# Connectors.net
KiCad netlist of a schematic drawn in Altium Designer
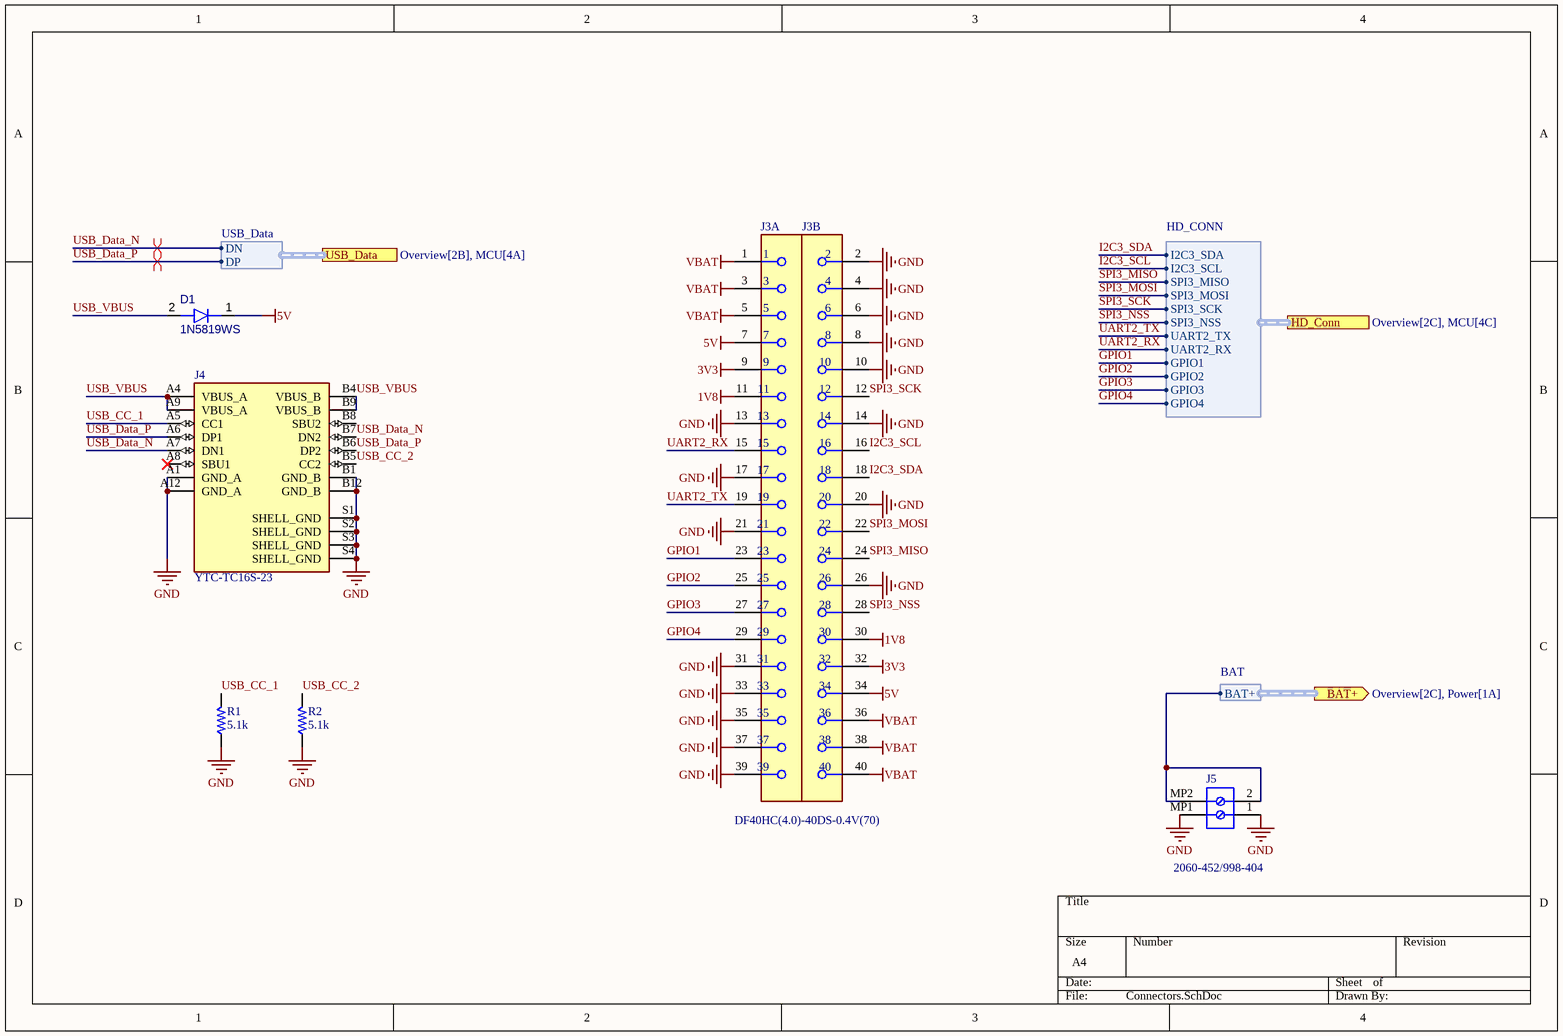
[diagram p0: Connectors.SchDoc]

(export (version "E")
  (design (tool "Eeschema 10.0.6"))
  (components
    (comp (ref "D1")
      (value "1N5819WS")
      (footprint "FP-477-02-IPC_C")
      (description "40V 600mV@1A 1A SOD-323  Schottky Barrier Diodes (SBD) ROHS")
      (fields (field (name "JLCPCB PART NUMBER") "C191023"))
      (libsource (lib "StrathSEDS") (part "DIODE-2"))
    )
    (comp (ref "J3")
      (value "DF40HC(4.0)-40DS-0.4V(70)")
      (footprint "FP-DF40HC_4_0_-40DS-0_4V-MFG")
      (fields (field (name "JLCPCB PART NUMBER") "C3654058"))
      (libsource (lib "StrathSEDS") (part "7acf1c4a8db21028d11741a46a6ec78"))
    )
    (comp (ref "J4")
      (value "YTC-TC16S-23")
      (footprint "VALCON_CSP-USC16-TR")
      (description "YTC-TC16S-23 USB Type C Surface Mount PCB Socket 3A")
      (fields (field (name "MP") "CSP-USC16-TR") (field (name "LCSC PART #") "C2927300"))
      (libsource (lib "StrathSEDS") (part "YTC-TC16S-23"))
    )
    (comp (ref "J5")
      (value "2060-452/998-404")
      (footprint "WAGO-2060-452_V")
      (description "Barrier Strip Terminal Block, 9A, 0.75mm2, 1 Row(s), 1 Deck(s)")
      (fields (field (name "JLCPCB PART NUMBER") "C2765055"))
      (libsource (lib "StrathSEDS") (part "CN-1P-2F-TB2"))
    )
    (comp (ref "R1")
      (value "5.1k")
      (footprint "RES-0402")
      (description "Resistor, 5.1kΩ, ±1%, 62.5mW, 50V, ±100ppm/℃, -55℃~+155℃, SMD 0402")
      (fields (field (name "JLCPCB BASIC PART") "Yes") (field (name "TOLERANCE") "1%"))
      (libsource (lib "StrathSEDS") (part "1206W4F7500T5E"))
    )
    (comp (ref "R2")
      (value "5.1k")
      (footprint "RES-0402")
      (description "Resistor, 5.1kΩ, ±1%, 62.5mW, 50V, ±100ppm/℃, -55℃~+155℃, SMD 0402")
      (fields (field (name "JLCPCB BASIC PART") "Yes") (field (name "TOLERANCE") "1%"))
      (libsource (lib "StrathSEDS") (part "1206W4F7500T5E"))
    )
  )
  (nets
    (net (code "4") (name "/GPIO1") (class "Default")
      (node (ref "J3") (pin "23") (pinfunction "23_23") (pintype "passive"))
    )
    (net (code "5") (name "/GPIO2") (class "Default")
      (node (ref "J3") (pin "25") (pinfunction "25_25") (pintype "passive"))
    )
    (net (code "6") (name "/GPIO3") (class "Default")
      (node (ref "J3") (pin "27") (pinfunction "27_27") (pintype "passive"))
    )
    (net (code "7") (name "/GPIO4") (class "Default")
      (node (ref "J3") (pin "29") (pinfunction "29_29") (pintype "passive"))
    )
    (net (code "8") (name "/I2C3_SCL") (class "Default")
      (node (ref "J3") (pin "16") (pinfunction "16_16") (pintype "passive"))
    )
    (net (code "9") (name "/I2C3_SDA") (class "Default")
      (node (ref "J3") (pin "18") (pinfunction "18_18") (pintype "passive"))
    )
    (net (code "10") (name "/SPI3_MISO") (class "Default")
      (node (ref "J3") (pin "24") (pinfunction "24_24") (pintype "passive"))
    )
    (net (code "11") (name "/SPI3_MOSI") (class "Default")
      (node (ref "J3") (pin "22") (pinfunction "22_22") (pintype "passive"))
    )
    (net (code "12") (name "/SPI3_NSS") (class "Default")
      (node (ref "J3") (pin "28") (pinfunction "28_28") (pintype "passive"))
    )
    (net (code "13") (name "/SPI3_SCK") (class "Default")
      (node (ref "J3") (pin "12") (pinfunction "12_12") (pintype "passive"))
    )
    (net (code "14") (name "/UART2_RX") (class "Default")
      (node (ref "J3") (pin "15") (pinfunction "15_15") (pintype "passive"))
    )
    (net (code "15") (name "/UART2_TX") (class "Default")
      (node (ref "J3") (pin "19") (pinfunction "19_19") (pintype "passive"))
    )
    (net (code "16") (name "/USB_CC_1") (class "Default")
      (node (ref "J4") (pin "A5") (pinfunction "CC1_A5") (pintype "bidirectional"))
      (node (ref "R1") (pin "2") (pinfunction "2_2") (pintype "passive"))
    )
    (net (code "17") (name "/USB_CC_2") (class "Default")
      (node (ref "J4") (pin "B5") (pinfunction "CC2_B5") (pintype "bidirectional"))
      (node (ref "R2") (pin "2") (pinfunction "2_2") (pintype "passive"))
    )
    (net (code "18") (name "/USB_Data_N") (class "Default")
      (node (ref "J4") (pin "A7") (pinfunction "DN1_A7") (pintype "bidirectional"))
      (node (ref "J4") (pin "B7") (pinfunction "DN2_B7") (pintype "bidirectional"))
    )
    (net (code "19") (name "/USB_Data_P") (class "Default")
      (node (ref "J4") (pin "A6") (pinfunction "DP1_A6") (pintype "bidirectional"))
      (node (ref "J4") (pin "B6") (pinfunction "DP2_B6") (pintype "bidirectional"))
    )
    (net (code "20") (name "/USB_VBUS") (class "Default")
      (node (ref "D1") (pin "2") (pinfunction "A_2") (pintype "passive"))
      (node (ref "J4") (pin "A4") (pinfunction "VBUS_A_A4") (pintype "power_in"))
      (node (ref "J4") (pin "A9") (pinfunction "VBUS_A_A9") (pintype "power_in"))
      (node (ref "J4") (pin "B4") (pinfunction "VBUS_B_B4") (pintype "power_in"))
      (node (ref "J4") (pin "B9") (pinfunction "VBUS_B_B9") (pintype "power_in"))
    )
    (net (code "24") (name "1V8") (class "Default")
      (node (ref "J3") (pin "11") (pinfunction "11_11") (pintype "passive"))
      (node (ref "J3") (pin "30") (pinfunction "30_30") (pintype "passive"))
    )
    (net (code "25") (name "3V3") (class "Default")
      (node (ref "J3") (pin "32") (pinfunction "32_32") (pintype "passive"))
      (node (ref "J3") (pin "9") (pinfunction "9_9") (pintype "passive"))
    )
    (net (code "26") (name "5V") (class "Default")
      (node (ref "D1") (pin "1") (pinfunction "K_1") (pintype "passive"))
      (node (ref "J3") (pin "34") (pinfunction "34_34") (pintype "passive"))
      (node (ref "J3") (pin "7") (pinfunction "7_7") (pintype "passive"))
    )
    (net (code "27") (name "GND") (class "Default")
      (node (ref "J3") (pin "10") (pinfunction "10_10") (pintype "passive"))
      (node (ref "J3") (pin "13") (pinfunction "13_13") (pintype "passive"))
      (node (ref "J3") (pin "14") (pinfunction "14_14") (pintype "passive"))
      (node (ref "J3") (pin "17") (pinfunction "17_17") (pintype "passive"))
      (node (ref "J3") (pin "2") (pinfunction "2_2") (pintype "passive"))
      (node (ref "J3") (pin "20") (pinfunction "20_20") (pintype "passive"))
      (node (ref "J3") (pin "21") (pinfunction "21_21") (pintype "passive"))
      (node (ref "J3") (pin "26") (pinfunction "26_26") (pintype "passive"))
      (node (ref "J3") (pin "31") (pinfunction "31_31") (pintype "passive"))
      (node (ref "J3") (pin "33") (pinfunction "33_33") (pintype "passive"))
      (node (ref "J3") (pin "35") (pinfunction "35_35") (pintype "passive"))
      (node (ref "J3") (pin "37") (pinfunction "37_37") (pintype "passive"))
      (node (ref "J3") (pin "39") (pinfunction "39_39") (pintype "passive"))
      (node (ref "J3") (pin "4") (pinfunction "4_4") (pintype "passive"))
      (node (ref "J3") (pin "6") (pinfunction "6_6") (pintype "passive"))
      (node (ref "J3") (pin "8") (pinfunction "8_8") (pintype "passive"))
      (node (ref "J4") (pin "A1") (pinfunction "GND_A_A1") (pintype "power_in"))
      (node (ref "J4") (pin "A12") (pinfunction "GND_A_A12") (pintype "power_in"))
      (node (ref "J4") (pin "B1") (pinfunction "GND_B_B1") (pintype "power_in"))
      (node (ref "J4") (pin "B12") (pinfunction "GND_B_B12") (pintype "power_in"))
      (node (ref "J4") (pin "S1") (pinfunction "SHELL_GND_S1") (pintype "power_in"))
      (node (ref "J4") (pin "S2") (pinfunction "SHELL_GND_S2") (pintype "power_in"))
      (node (ref "J4") (pin "S3") (pinfunction "SHELL_GND_S3") (pintype "power_in"))
      (node (ref "J4") (pin "S4") (pinfunction "SHELL_GND_S4") (pintype "power_in"))
      (node (ref "J5") (pin "1") (pinfunction "1_1") (pintype "passive"))
      (node (ref "J5") (pin "MP1") (pinfunction "MP1_MP1") (pintype "passive"))
      (node (ref "R1") (pin "1") (pinfunction "1_1") (pintype "passive"))
      (node (ref "R2") (pin "1") (pinfunction "1_1") (pintype "passive"))
    )
    (net (code "28") (name "Net-(J5-Pad2)") (class "Default")
      (node (ref "J5") (pin "2") (pinfunction "2_2") (pintype "passive"))
      (node (ref "J5") (pin "MP2") (pinfunction "MP2_MP2") (pintype "passive"))
    )
    (net (code "29") (name "VBAT") (class "Default")
      (node (ref "J3") (pin "1") (pinfunction "1_1") (pintype "passive"))
      (node (ref "J3") (pin "3") (pinfunction "3_3") (pintype "passive"))
      (node (ref "J3") (pin "36") (pinfunction "36_36") (pintype "passive"))
      (node (ref "J3") (pin "38") (pinfunction "38_38") (pintype "passive"))
      (node (ref "J3") (pin "40") (pinfunction "40_40") (pintype "passive"))
      (node (ref "J3") (pin "5") (pinfunction "5_5") (pintype "passive"))
    )
    (net (code "30") (name "unconnected-(J4-SBU1-PadA8)") (class "Default")
      (node (ref "J4") (pin "A8") (pinfunction "SBU1_A8") (pintype "bidirectional+no_connect"))
    )
    (net (code "31") (name "unconnected-(J4-SBU2-PadB8)") (class "Default")
      (node (ref "J4") (pin "B8") (pinfunction "SBU2_B8") (pintype "bidirectional"))
    )
  )
)
